# ProPrj___2025-02-25.net
KiCad netlist of a schematic drawn in EasyEDA Pro
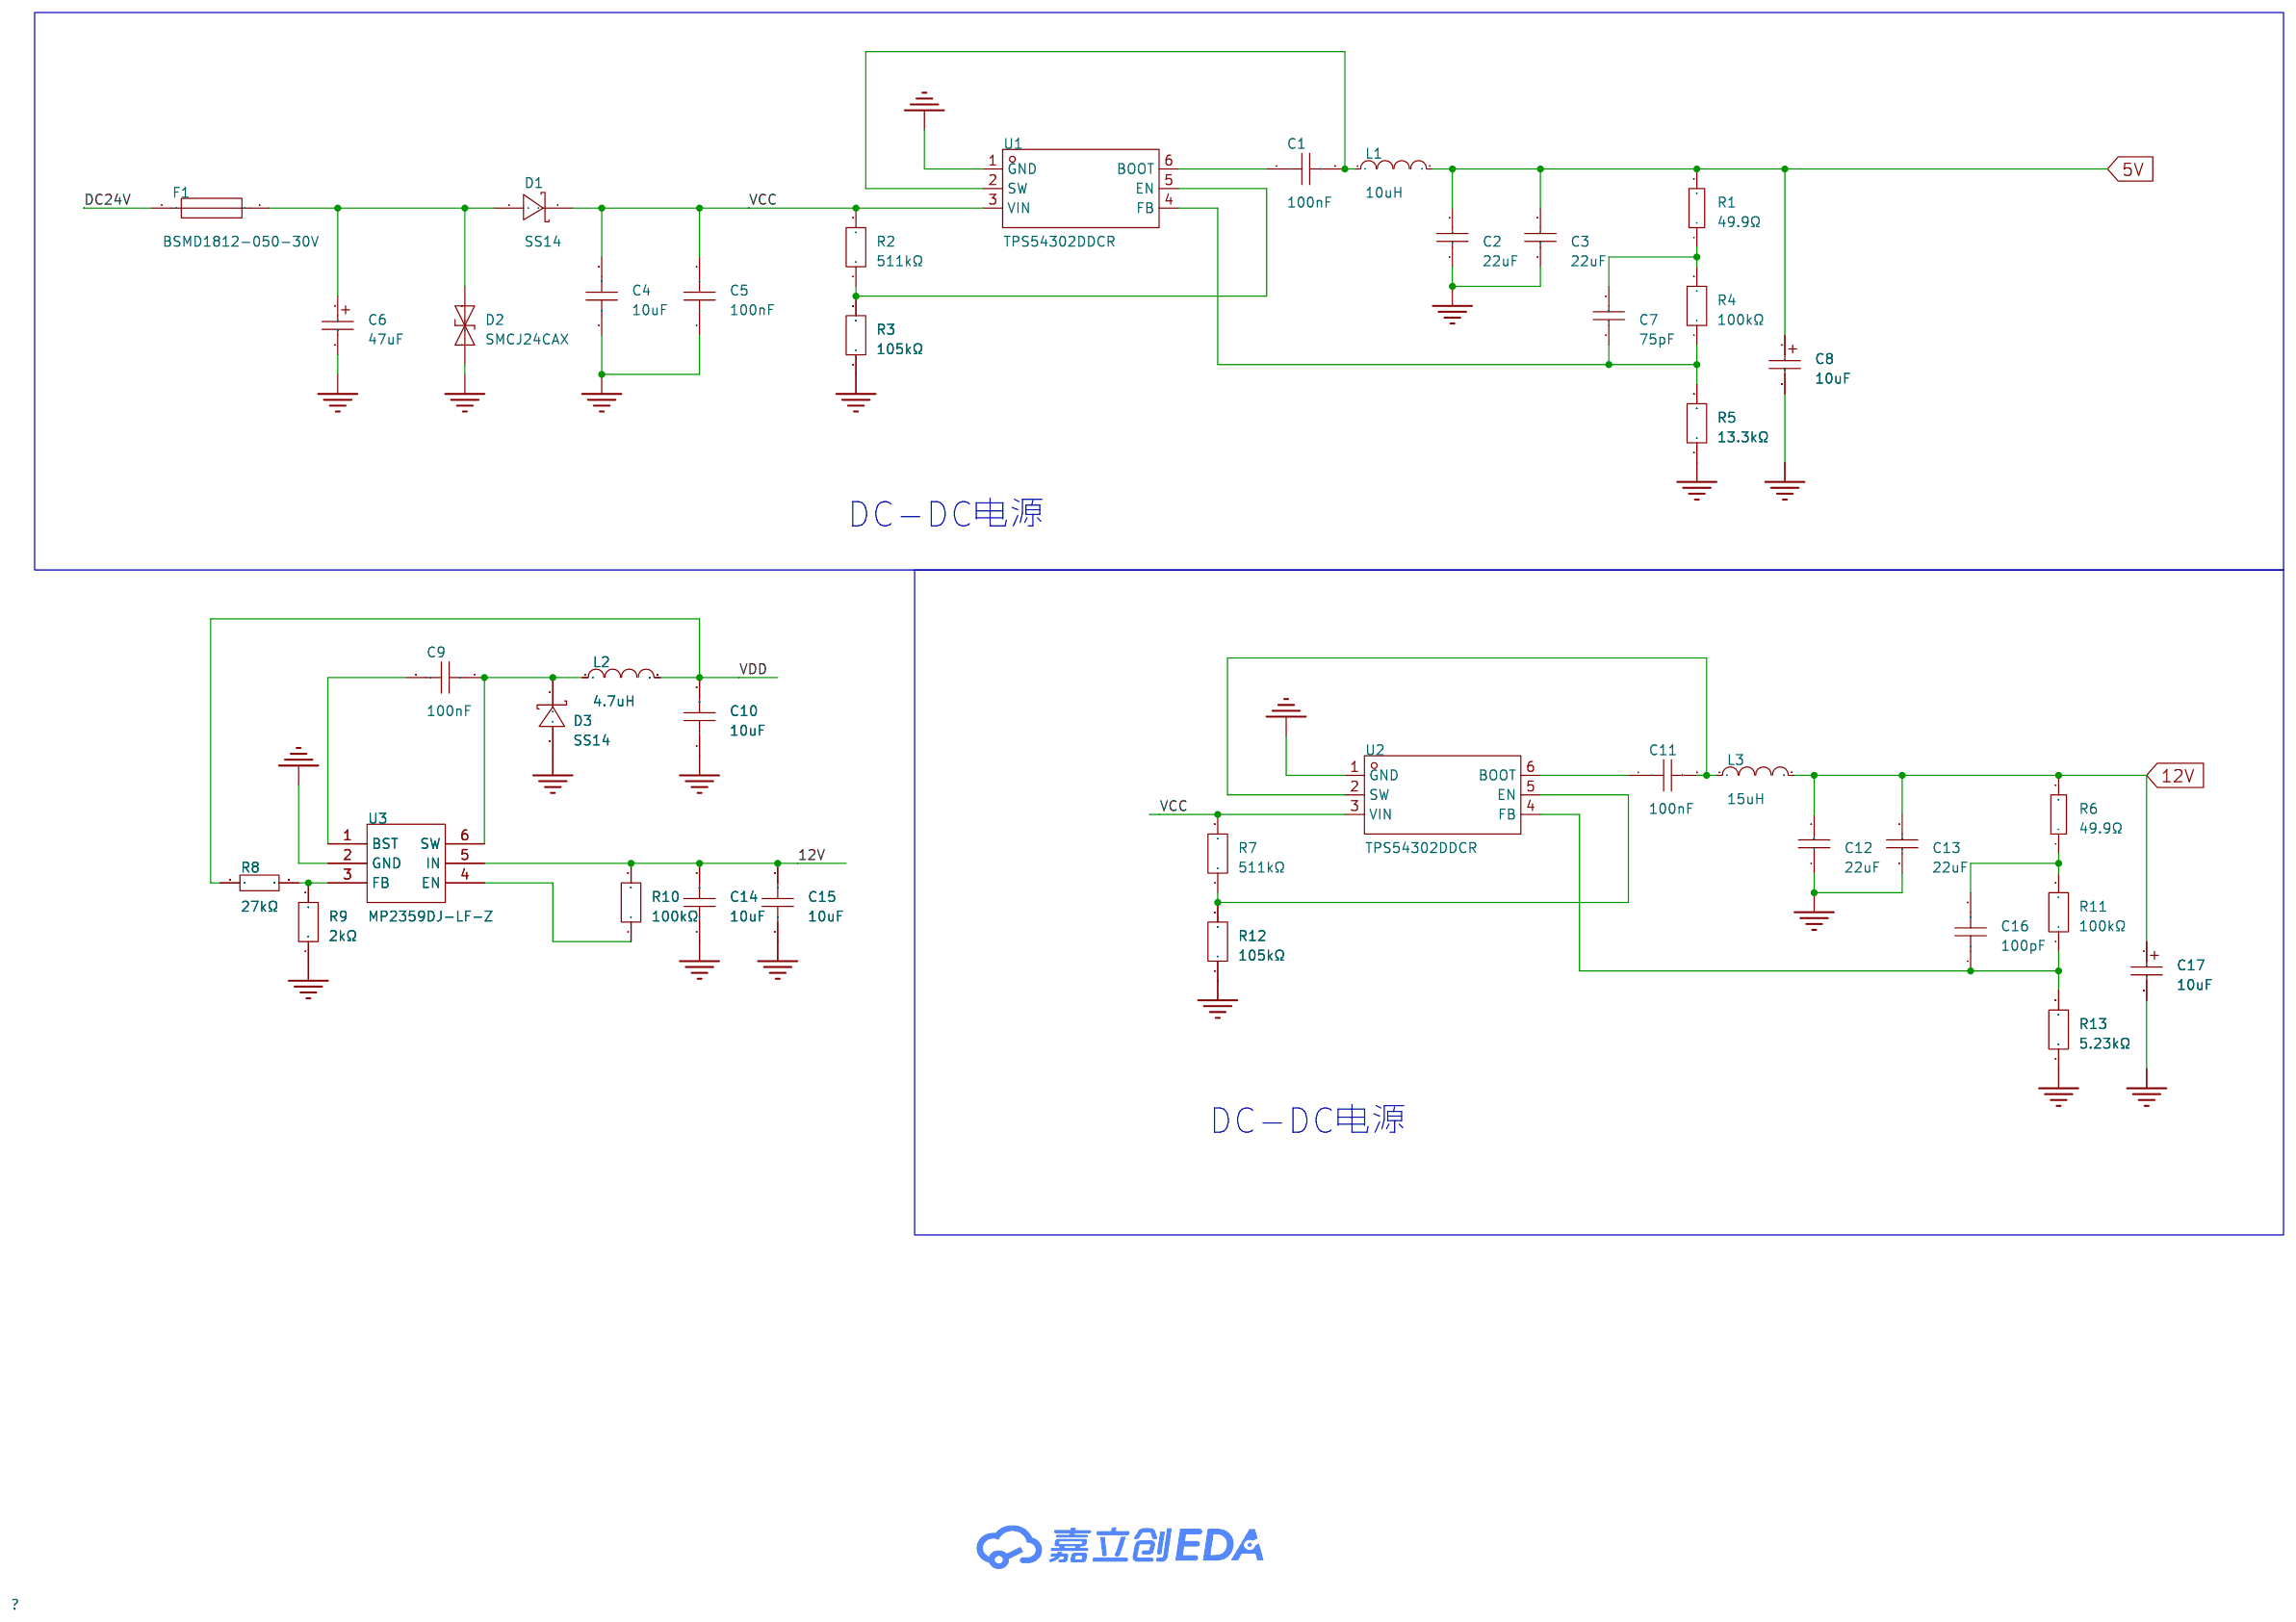
[diagram p0: P1]
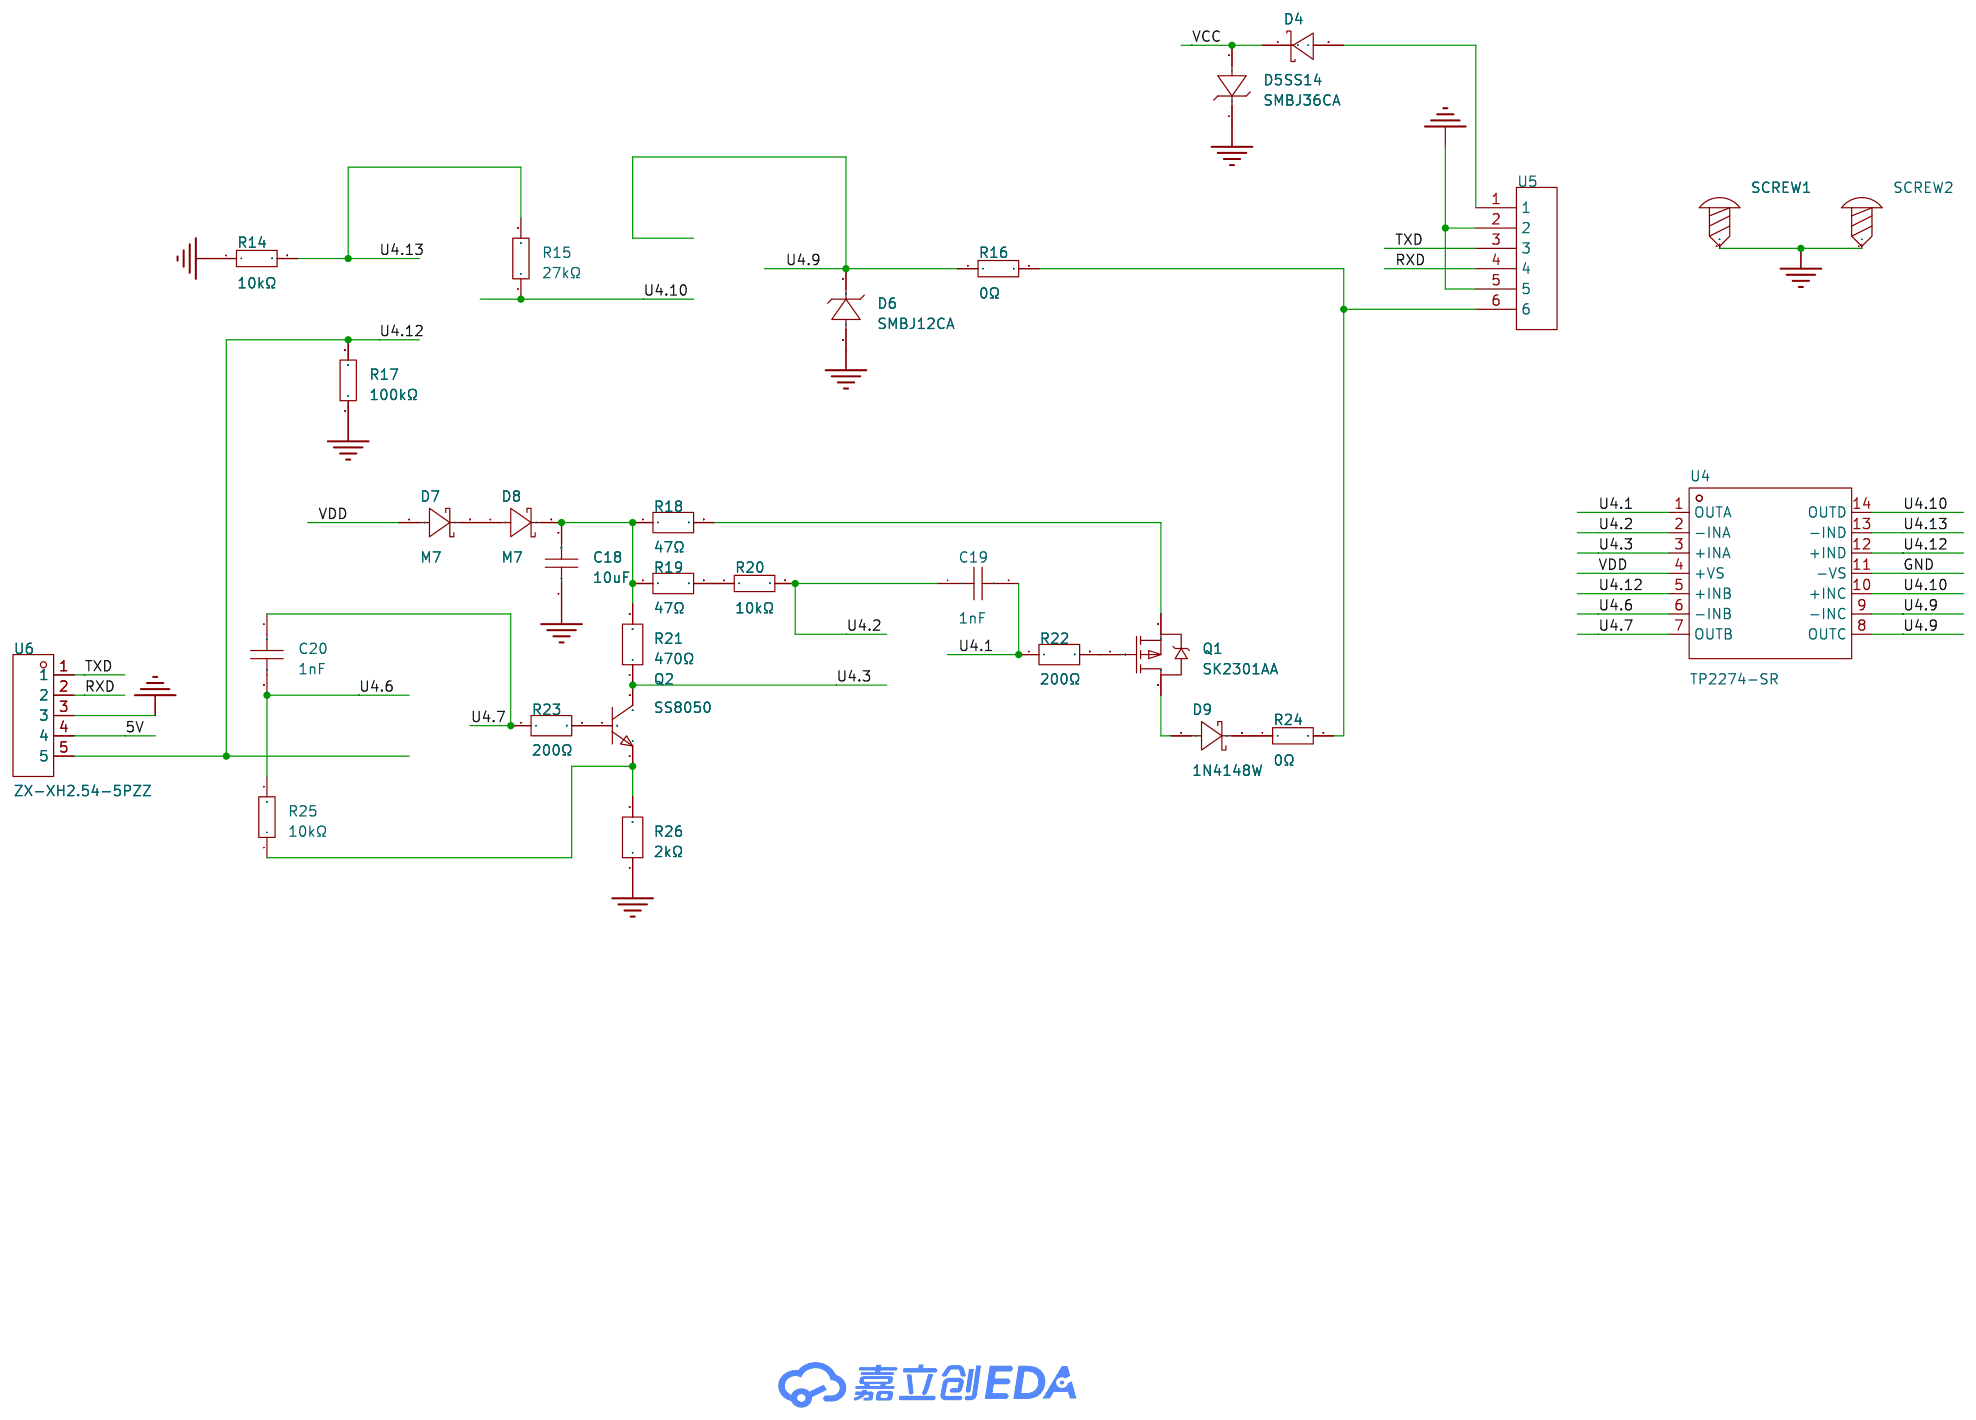
[diagram p1: P2]

(export (version "E")
  (design (tool "Eeschema 10.0.6"))
  (components
    (comp (ref "C1")
      (value "100nF")
      (footprint "easyedapro:C0402")
      (description "容值:100nF;精度:±10%;额定电压:50V;材质(温度系数):X7R;")
      (fields
        (field (name "Manufacturer Part") "GRM155R71H104KE14D")
        (field (name "Manufacturer") "muRata(村田)")
      )
      (libsource (lib "easyedapro") (part "GRM155R71H104KE14D"))
    )
    (comp (ref "C2")
      (value "22uF")
      (footprint "easyedapro:C0805")
      (description "容值:22uF;精度:±20%;额定电压:25V;材质(温度系数):X5R;")
      (fields
        (field (name "Manufacturer Part") "CC0805MKX5R8BB226")
        (field (name "Manufacturer") "YAGEO(国巨)")
      )
      (libsource (lib "easyedapro") (part "CC0805MKX5R8BB226"))
    )
    (comp (ref "C3")
      (value "22uF")
      (footprint "easyedapro:C0805")
      (description "容值:22uF;精度:±20%;额定电压:25V;材质(温度系数):X5R;")
      (fields
        (field (name "Manufacturer Part") "CC0805MKX5R8BB226")
        (field (name "Manufacturer") "YAGEO(国巨)")
      )
      (libsource (lib "easyedapro") (part "CC0805MKX5R8BB226"))
    )
    (comp (ref "C4")
      (value "10uF")
      (footprint "easyedapro:C0603")
      (description "容值:10uF;精度:±20%;额定电压:35V;材质(温度系数):X5R;")
      (fields
        (field (name "Manufacturer Part") "GRM188R6YA106MA73D")
        (field (name "Manufacturer") "muRata(村田)")
      )
      (libsource (lib "easyedapro") (part "GRM188R6YA106MA73D"))
    )
    (comp (ref "C5")
      (value "100nF")
      (footprint "easyedapro:C0402")
      (description "容值:100nF;精度:±10%;额定电压:35V;材质(温度系数):X7R;")
      (fields (field (name "Manufacturer Part") "CGA2B3X7R1V104KT0Y0F") (field (name "Manufacturer") "TDK"))
      (libsource (lib "easyedapro") (part "CGA2B3X7R1V104KT0Y0F"))
    )
    (comp (ref "C6")
      (value "47uF")
      (footprint "easyedapro:CAP-SMD_L7.3-W4.3-FD")
      (description "容值:47uF;精度:±10%;额定电压:35V;等效串联电阻:600mΩ@100kHz;")
      (fields (field (name "Manufacturer Part") "T491X476K035AT") (field (name "Manufacturer") "KEMET(基美)"))
      (libsource (lib "easyedapro") (part "T491X476K035AT"))
    )
    (comp (ref "C7")
      (value "75pF")
      (footprint "easyedapro:C0402")
      (description "容值:75pF;精度:±5%;额定电压:50V;材质(温度系数):NP0;")
      (fields
        (field (name "Manufacturer Part") "CC0402JRNPO9BN750")
        (field (name "Manufacturer") "YAGEO(国巨)")
      )
      (libsource (lib "easyedapro") (part "CC0402JRNPO9BN750"))
    )
    (comp (ref "C8")
      (value "10uF")
      (footprint "easyedapro:CASE-C_6032")
      (description "容值:10uF;精度:±10%;额定电压:35V;等效串联电阻:1.6Ω@100kHz;")
      (fields (field (name "Manufacturer Part") "TAJC106K035RNJ") (field (name "Manufacturer") "Kyocera AVX"))
      (libsource (lib "easyedapro") (part "TAJC106K035RNJ"))
    )
    (comp (ref "C9")
      (value "100nF")
      (footprint "easyedapro:C0402")
      (description "容值:100nF;精度:±10%;额定电压:35V;材质(温度系数):X7R;")
      (fields (field (name "Manufacturer Part") "CGA2B3X7R1V104KT0Y0F") (field (name "Manufacturer") "TDK"))
      (libsource (lib "easyedapro") (part "CGA2B3X7R1V104KT0Y0F"))
    )
    (comp (ref "C10")
      (value "10uF")
      (footprint "easyedapro:C0603")
      (description "容值:10uF;精度:±20%;额定电压:35V;材质(温度系数):X5R;")
      (fields
        (field (name "Manufacturer Part") "GRM188R6YA106MA73D")
        (field (name "Manufacturer") "muRata(村田)")
      )
      (libsource (lib "easyedapro") (part "GRM188R6YA106MA73D"))
    )
    (comp (ref "C11")
      (value "100nF")
      (footprint "easyedapro:C0402")
      (description "容值:100nF;精度:±10%;额定电压:50V;材质(温度系数):X7R;")
      (fields
        (field (name "Manufacturer Part") "GRM155R71H104KE14D")
        (field (name "Manufacturer") "muRata(村田)")
      )
      (libsource (lib "easyedapro") (part "GRM155R71H104KE14D"))
    )
    (comp (ref "C12")
      (value "22uF")
      (footprint "easyedapro:C0805")
      (description "容值:22uF;精度:±20%;额定电压:25V;材质(温度系数):X5R;")
      (fields
        (field (name "Manufacturer Part") "CC0805MKX5R8BB226")
        (field (name "Manufacturer") "YAGEO(国巨)")
      )
      (libsource (lib "easyedapro") (part "CC0805MKX5R8BB226"))
    )
    (comp (ref "C13")
      (value "22uF")
      (footprint "easyedapro:C0805")
      (description "容值:22uF;精度:±20%;额定电压:25V;材质(温度系数):X5R;")
      (fields
        (field (name "Manufacturer Part") "CC0805MKX5R8BB226")
        (field (name "Manufacturer") "YAGEO(国巨)")
      )
      (libsource (lib "easyedapro") (part "CC0805MKX5R8BB226"))
    )
    (comp (ref "C14")
      (value "10uF")
      (footprint "easyedapro:C0603")
      (description "容值:10uF;精度:±20%;额定电压:35V;材质(温度系数):X5R;")
      (fields
        (field (name "Manufacturer Part") "GRM188R6YA106MA73D")
        (field (name "Manufacturer") "muRata(村田)")
      )
      (libsource (lib "easyedapro") (part "GRM188R6YA106MA73D"))
    )
    (comp (ref "C15")
      (value "10uF")
      (footprint "easyedapro:C0603")
      (description "容值:10uF;精度:±20%;额定电压:35V;材质(温度系数):X5R;")
      (fields
        (field (name "Manufacturer Part") "GRM188R6YA106MA73D")
        (field (name "Manufacturer") "muRata(村田)")
      )
      (libsource (lib "easyedapro") (part "GRM188R6YA106MA73D"))
    )
    (comp (ref "C16")
      (value "100pF")
      (footprint "easyedapro:C0402")
      (description "容值:100pF;精度:±10%;额定电压:25V;材质(温度系数):X7R;")
      (fields
        (field (name "Manufacturer Part") "CC0402KRX7R8BB101")
        (field (name "Manufacturer") "YAGEO(国巨)")
      )
      (libsource (lib "easyedapro") (part "CC0402KRX7R8BB101"))
    )
    (comp (ref "C17")
      (value "10uF")
      (footprint "easyedapro:CASE-C_6032")
      (description "容值:10uF;精度:±10%;额定电压:35V;等效串联电阻:1.6Ω@100kHz;")
      (fields (field (name "Manufacturer Part") "TAJC106K035RNJ") (field (name "Manufacturer") "Kyocera AVX"))
      (libsource (lib "easyedapro") (part "TAJC106K035RNJ"))
    )
    (comp (ref "D1")
      (value "SS14")
      (footprint "easyedapro:SMA_L4.2-W2.6-LS5.3-RD")
      (description "二极管配置:独立式;正向压降(Vf):550mV@1A;直流反向耐压(Vr):40V;整流电流:1A;")
      (fields (field (name "Manufacturer") "MDD(辰达半导体)"))
      (libsource (lib "easyedapro") (part "SS14"))
    )
    (comp (ref "D2")
      (value "SMCJ24CAX")
      (footprint "easyedapro:SMC_L6.9-W5.9-LS7.9-BI")
      (description "VRWM24(V)/VBR(Min)@IT26.7(V)/VBR(Max)@IT30.7(V)/IT1(mA)/IR5(uA)/VC(Max)38.9(V)/Ipp(Max)38.6(A)")
      (fields (field (name "Manufacturer") "晶扬电子"))
      (libsource (lib "easyedapro") (part "SMCJ24CA_C3038088"))
    )
    (comp (ref "D3")
      (value "SS14")
      (footprint "easyedapro:SMA_L4.3-W2.6-LS5.2-RD")
      (description "正向压降(Vf):500mV@1A;直流反向耐压(Vr):40V;整流电流:1A;")
      (fields (field (name "Manufacturer") "onsemi(安森美)"))
      (libsource (lib "easyedapro") (part "SS14_C83852"))
    )
    (comp (ref "F1")
      (value "BSMD1812-050-30V")
      (footprint "easyedapro:F1812")
      (description "最大电压:30V;最大电流:40A;保持电流:500mA;跳闸电流:1A;")
      (fields (field (name "Manufacturer") "BHFUSE(佰宏)"))
      (libsource (lib "easyedapro") (part "BSMD1812-050-30V"))
    )
    (comp (ref "L1")
      (value "10uH")
      (footprint "easyedapro:IND-SMD_L4.4-W4.2")
      (description "电感值:10uH;精度:±20%;额定电流:1.6A;饱和电流(Isat):2.2A;类型:一体成型电感;")
      (fields (field (name "Manufacturer Part") "FXL0420-100-M") (field (name "Manufacturer") "cjiang(长江微电)"))
      (libsource (lib "easyedapro") (part "FXL0420-100-M"))
    )
    (comp (ref "L2")
      (value "4.7uH")
      (footprint "easyedapro:IND-SMD_L7.0-W6.6")
      (description "电感值:4.7uH;精度:±20%;额定电流:6A;饱和电流(Isat):9A;类型:一体成型电感;")
      (fields (field (name "Manufacturer Part") "FXL0630-4R7-M") (field (name "Manufacturer") "cjiang(长江微电)"))
      (libsource (lib "easyedapro") (part "FXL0630-4R7-M"))
    )
    (comp (ref "L3")
      (value "15uH")
      (footprint "easyedapro:IND-SMD_L4.0-W4.0")
      (description "电感值:15uH;精度:±20%;额定电流:1.2A;饱和电流(Isat):2.8A;")
      (fields
        (field (name "Manufacturer Part") "FHD4020S-150MT")
        (field (name "Manufacturer") "cjiang(长江微电)")
      )
      (libsource (lib "easyedapro") (part "FHD4020S-150MT"))
    )
    (comp (ref "R1")
      (value "49.9Ω")
      (footprint "easyedapro:R0402")
      (description "电阻类型:薄膜电阻;阻值:49.9Ω;精度:±0.1%;功率:60mW;最大工作电压:75V;温度系数:±25ppm/°C;")
      (fields (field (name "Manufacturer Part") "PTFR0402B49R9P9") (field (name "Manufacturer") "RESI(开步睿思)"))
      (libsource (lib "easyedapro") (part "PTFR0402B49R9P9"))
    )
    (comp (ref "R2")
      (value "511kΩ")
      (footprint "easyedapro:R0603")
      (description "电阻类型:薄膜电阻;阻值:511kΩ;精度:±0.1%;功率:100mW;最大工作电压:75V;温度系数:±25ppm/°C;")
      (fields (field (name "Manufacturer Part") "ARG03BTC5113") (field (name "Manufacturer") "Viking(光颉)"))
      (libsource (lib "easyedapro") (part "ARG03BTC5113"))
    )
    (comp (ref "R3")
      (value "105kΩ")
      (footprint "easyedapro:R0402")
      (description "电阻类型:薄膜电阻;阻值:105kΩ;精度:±0.1%;功率:62.5mW;温度系数:±25ppm/°C;")
      (fields (field (name "Manufacturer Part") "RT0402BRD07105KL") (field (name "Manufacturer") "YAGEO(国巨)"))
      (libsource (lib "easyedapro") (part "RT0402BRD07105KL"))
    )
    (comp (ref "R4")
      (value "100kΩ")
      (footprint "easyedapro:R0402")
      (description "电阻类型:薄膜电阻;阻值:100kΩ;精度:±0.1%;功率:62.5mW;最大工作电压:50V;温度系数:±25ppm/°C;")
      (fields (field (name "Manufacturer Part") "RT0402BRD07100KL") (field (name "Manufacturer") "YAGEO(国巨)"))
      (libsource (lib "easyedapro") (part "RT0402BRD07100KL"))
    )
    (comp (ref "R5")
      (value "13.3kΩ")
      (footprint "easyedapro:R0603")
      (description "电阻类型:薄膜电阻;阻值:13.3kΩ;精度:±0.1%;功率:100mW;最大工作电压:75V;温度系数:±25ppm/°C;")
      (fields (field (name "Manufacturer Part") "RT0603BRD0713K3L") (field (name "Manufacturer") "YAGEO(国巨)"))
      (libsource (lib "easyedapro") (part "RT0603BRD0713K3L"))
    )
    (comp (ref "R6")
      (value "49.9Ω")
      (footprint "easyedapro:R0402")
      (description "电阻类型:薄膜电阻;阻值:49.9Ω;精度:±0.1%;功率:60mW;最大工作电压:75V;温度系数:±25ppm/°C;")
      (fields (field (name "Manufacturer Part") "PTFR0402B49R9P9") (field (name "Manufacturer") "RESI(开步睿思)"))
      (libsource (lib "easyedapro") (part "PTFR0402B49R9P9"))
    )
    (comp (ref "R7")
      (value "511kΩ")
      (footprint "easyedapro:R0603")
      (description "电阻类型:薄膜电阻;阻值:511kΩ;精度:±0.1%;功率:100mW;最大工作电压:75V;温度系数:±25ppm/°C;")
      (fields (field (name "Manufacturer Part") "ARG03BTC5113") (field (name "Manufacturer") "Viking(光颉)"))
      (libsource (lib "easyedapro") (part "ARG03BTC5113"))
    )
    (comp (ref "R8")
      (value "27kΩ")
      (footprint "easyedapro:R0603")
      (description "电阻类型:薄膜电阻;阻值:27kΩ;精度:±0.1%;功率:100mW;最大工作电压:75V;温度系数:±50ppm/°C;")
      (fields (field (name "Manufacturer Part") "RT0603BRE0727KL") (field (name "Manufacturer") "YAGEO(国巨)"))
      (libsource (lib "easyedapro") (part "RT0603BRE0727KL"))
    )
    (comp (ref "R9")
      (value "2kΩ")
      (footprint "easyedapro:R0603")
      (description "电阻类型:薄膜电阻;阻值:2kΩ;精度:±0.1%;功率:100mW;温度系数:±25ppm/°C;")
      (fields (field (name "Manufacturer Part") "RT0603BRD072KL") (field (name "Manufacturer") "YAGEO(国巨)"))
      (libsource (lib "easyedapro") (part "RT0603BRD072KL"))
    )
    (comp (ref "R10")
      (value "100kΩ")
      (footprint "easyedapro:R0402")
      (description "电阻类型:薄膜电阻;阻值:100kΩ;精度:±0.1%;功率:62.5mW;最大工作电压:50V;温度系数:±25ppm/°C;")
      (fields (field (name "Manufacturer Part") "RT0402BRD07100KL") (field (name "Manufacturer") "YAGEO(国巨)"))
      (libsource (lib "easyedapro") (part "RT0402BRD07100KL"))
    )
    (comp (ref "R11")
      (value "100kΩ")
      (footprint "easyedapro:R0402")
      (description "电阻类型:薄膜电阻;阻值:100kΩ;精度:±0.1%;功率:62.5mW;最大工作电压:50V;温度系数:±25ppm/°C;")
      (fields (field (name "Manufacturer Part") "RT0402BRD07100KL") (field (name "Manufacturer") "YAGEO(国巨)"))
      (libsource (lib "easyedapro") (part "RT0402BRD07100KL"))
    )
    (comp (ref "R12")
      (value "105kΩ")
      (footprint "easyedapro:R0402")
      (description "电阻类型:薄膜电阻;阻值:105kΩ;精度:±0.1%;功率:62.5mW;温度系数:±25ppm/°C;")
      (fields (field (name "Manufacturer Part") "RT0402BRD07105KL") (field (name "Manufacturer") "YAGEO(国巨)"))
      (libsource (lib "easyedapro") (part "RT0402BRD07105KL"))
    )
    (comp (ref "R13")
      (value "5.23kΩ")
      (footprint "easyedapro:R0603")
      (description "电阻类型:薄膜电阻;阻值:5.23kΩ;精度:±0.1%;功率:100mW;温度系数:±25ppm/°C;")
      (fields (field (name "Manufacturer Part") "RT0603BRD075K23L") (field (name "Manufacturer") "YAGEO(国巨)"))
      (libsource (lib "easyedapro") (part "RT0603BRD075K23L"))
    )
    (comp (ref "U1")
      (value "TPS54302DDCR")
      (footprint "easyedapro:SOT-23-6_L2.9-W1.6-P0.95-LS2.8-BL")
      (description "功能类型:降压型;输出类型:固定;工作电压:4.5V~28V;输出电压:5V;输出电流:3A;")
      (fields (field (name "Manufacturer") "TI(德州仪器)"))
      (libsource (lib "easyedapro") (part "TPS54302DDCR_C311983"))
    )
    (comp (ref "U2")
      (value "TPS54302DDCR")
      (footprint "easyedapro:SOT-23-6_L2.9-W1.6-P0.95-LS2.8-BL")
      (description "功能类型:降压型;输出类型:固定;工作电压:4.5V~28V;输出电压:5V;输出电流:3A;")
      (fields (field (name "Manufacturer") "TI(德州仪器)"))
      (libsource (lib "easyedapro") (part "TPS54302DDCR_C311983"))
    )
    (comp (ref "U3")
      (value "MP2359DJ-LF-Z")
      (footprint "easyedapro:SOT-23-6_L2.9-W1.6-P0.95-LS2.8-BR")
      (description "功能类型:降压型;输出类型:可调;工作电压:4.5V~24V;输出电压:810mV~15V;输出电流:1.2A;")
      (fields (field (name "Manufacturer") "MPS(芯源)"))
      (libsource (lib "easyedapro") (part "MP2359DJ-LF-Z"))
    )
    (comp (ref "C18")
      (value "10uF")
      (footprint "easyedapro:C0603")
      (description "容值:10uF;精度:±20%;额定电压:35V;材质(温度系数):X5R;")
      (fields
        (field (name "Manufacturer Part") "HGC0603R5106M350NTHJ")
        (field (name "Manufacturer") "Chinocera(华瓷)")
      )
      (libsource (lib "easyedapro") (part "HGC0603R5106M350NTHJ"))
    )
    (comp (ref "C19")
      (value "1nF")
      (footprint "easyedapro:C0603")
      (description "容值:1nF;精度:±10%;额定电压:25V;材质(温度系数):X7R;")
      (fields
        (field (name "Manufacturer Part") "CC0603KRX7R8BB102")
        (field (name "Manufacturer") "YAGEO(国巨)")
      )
      (libsource (lib "easyedapro") (part "CC0603KRX7R8BB102"))
    )
    (comp (ref "C20")
      (value "1nF")
      (footprint "easyedapro:C0603")
      (description "容值:1nF;精度:±10%;额定电压:25V;材质(温度系数):X7R;")
      (fields
        (field (name "Manufacturer Part") "CC0603KRX7R8BB102")
        (field (name "Manufacturer") "YAGEO(国巨)")
      )
      (libsource (lib "easyedapro") (part "CC0603KRX7R8BB102"))
    )
    (comp (ref "D4")
      (value "SS14")
      (footprint "easyedapro:SMA_L4.3-W2.6-LS5.2-RD")
      (description "正向压降(Vf):500mV@1A;直流反向耐压(Vr):40V;整流电流:1A;")
      (fields (field (name "Manufacturer") "onsemi(安森美)"))
      (libsource (lib "easyedapro") (part "SS14_C83852"))
    )
    (comp (ref "D5")
      (value "SMBJ36CA")
      (footprint "easyedapro:SMB_L4.6-W3.6-LS5.4-RD")
      (description "极性:双向;反向截止电压(Vrwm):36V;钳位电压:58.1V;峰值脉冲电流(Ipp):10.33A;峰值脉冲功率(Ppp):600W;击穿电压:40V;")
      (fields (field (name "Manufacturer") "宏嘉诚"))
      (libsource (lib "easyedapro") (part "SMBJ36CA_C19077589"))
    )
    (comp (ref "D6")
      (value "SMBJ12CA")
      (footprint "easyedapro:SMB_L4.6-W3.6-LS5.4-RD")
      (fields (field (name "Manufacturer") "宏迦橙"))
      (libsource (lib "easyedapro") (part "SMBJ12CA_C19077566"))
    )
    (comp (ref "D7")
      (value "M7")
      (footprint "easyedapro:SMA_L4.3-W2.6-LS5.0-FD")
      (description "二极管配置:独立式;正向压降(Vf):1.1V@1A;直流反向耐压(Vr):1kV;整流电流:1A;")
      (fields (field (name "Manufacturer") "宏迦橙"))
      (libsource (lib "easyedapro") (part "M7_C7420350"))
    )
    (comp (ref "D8")
      (value "M7")
      (footprint "easyedapro:SMA_L4.3-W2.6-LS5.0-FD")
      (description "二极管配置:独立式;正向压降(Vf):1.1V@1A;直流反向耐压(Vr):1kV;整流电流:1A;")
      (fields (field (name "Manufacturer") "宏迦橙"))
      (libsource (lib "easyedapro") (part "M7_C7420350"))
    )
    (comp (ref "D9")
      (value "1N4148W")
      (footprint "easyedapro:SOD-123_L2.7-W1.6-LS3.7-FD")
      (description "二极管配置:独立式;正向压降(Vf):1.25V@150mA;直流反向耐压(Vr):100V;整流电流:150mA;反向恢复时间(trr):4ns;")
      (fields (field (name "Manufacturer") "宏迦橙"))
      (libsource (lib "easyedapro") (part "1N4148W_C7420318"))
    )
    (comp (ref "Q1")
      (value "SK2301AA")
      (footprint "easyedapro:SOT-23-3_L2.9-W1.6-P1.90-LS2.8-BR")
      (fields (field (name "Manufacturer") "SHIKUES(时科)"))
      (libsource (lib "easyedapro") (part "SK2301AA"))
    )
    (comp (ref "Q2")
      (value "SS8050")
      (footprint "easyedapro:SOT-23-3_L2.9-W1.3-P1.90-LS2.4-BR")
      (description "晶体管类型:NPN;集电极电流(Ic):1.5A;集射极击穿电压(Vceo):25V;功率(Pd):300mW;直流电流增益(hFE@Ic,Vce):120@100mA,1.0V;")
      (fields (field (name "Manufacturer") "宏迦橙"))
      (libsource (lib "easyedapro") (part "SS8050_C7420370"))
    )
    (comp (ref "R14")
      (value "10kΩ")
      (footprint "easyedapro:R0603")
      (description "电阻类型:薄膜电阻;阻值:10kΩ;精度:±0.1%;功率:100mW;最大工作电压:75V;温度系数:±25ppm/°C;")
      (fields (field (name "Manufacturer Part") "RT0603BRD0710KL") (field (name "Manufacturer") "YAGEO(国巨)"))
      (libsource (lib "easyedapro") (part "RT0603BRD0710KL"))
    )
    (comp (ref "R15")
      (value "27kΩ")
      (footprint "easyedapro:R0603")
      (description "电阻类型:薄膜电阻;阻值:27kΩ;精度:±0.1%;功率:100mW;最大工作电压:75V;温度系数:±50ppm/°C;")
      (fields (field (name "Manufacturer Part") "RT0603BRE0727KL") (field (name "Manufacturer") "YAGEO(国巨)"))
      (libsource (lib "easyedapro") (part "RT0603BRE0727KL"))
    )
    (comp (ref "R16")
      (value "0Ω")
      (footprint "easyedapro:R0603")
      (description "电阻类型:厚膜电阻;阻值:0Ω;精度:±1%;功率:100mW;最大工作电压:75V;温度系数:-;")
      (fields (field (name "Manufacturer Part") "RC0603FR-070RL") (field (name "Manufacturer") "YAGEO(国巨)"))
      (libsource (lib "easyedapro") (part "RC0603FR-070RL"))
    )
    (comp (ref "R17")
      (value "100kΩ")
      (footprint "easyedapro:R0603")
      (description "电阻类型:薄膜电阻;阻值:100kΩ;精度:±0.1%;功率:100mW;最大工作电压:75V;温度系数:±25ppm/°C;")
      (fields (field (name "Manufacturer Part") "RT0603BRD07100KL") (field (name "Manufacturer") "YAGEO(国巨)"))
      (libsource (lib "easyedapro") (part "RT0603BRD07100KL"))
    )
    (comp (ref "R18")
      (value "47Ω")
      (footprint "easyedapro:R0603")
      (description "电阻类型:薄膜电阻;阻值:47Ω;精度:±0.1%;功率:100mW;最大工作电压:75V;温度系数:±50ppm/°C;")
      (fields (field (name "Manufacturer Part") "RT0603BRE0747RL") (field (name "Manufacturer") "YAGEO(国巨)"))
      (libsource (lib "easyedapro") (part "RT0603BRE0747RL"))
    )
    (comp (ref "R19")
      (value "47Ω")
      (footprint "easyedapro:R0603")
      (description "电阻类型:薄膜电阻;阻值:47Ω;精度:±0.1%;功率:100mW;最大工作电压:75V;温度系数:±50ppm/°C;")
      (fields (field (name "Manufacturer Part") "RT0603BRE0747RL") (field (name "Manufacturer") "YAGEO(国巨)"))
      (libsource (lib "easyedapro") (part "RT0603BRE0747RL"))
    )
    (comp (ref "R20")
      (value "10kΩ")
      (footprint "easyedapro:R0603")
      (description "电阻类型:薄膜电阻;阻值:10kΩ;精度:±0.1%;功率:100mW;最大工作电压:75V;温度系数:±25ppm/°C;")
      (fields (field (name "Manufacturer Part") "RT0603BRD0710KL") (field (name "Manufacturer") "YAGEO(国巨)"))
      (libsource (lib "easyedapro") (part "RT0603BRD0710KL"))
    )
    (comp (ref "R21")
      (value "470Ω")
      (footprint "easyedapro:R0603")
      (description "电阻类型:薄膜电阻;阻值:470Ω;精度:±0.1%;功率:100mW;最大工作电压:75V;温度系数:±25ppm/°C;")
      (fields (field (name "Manufacturer Part") "RT0603BRD07470RL") (field (name "Manufacturer") "YAGEO(国巨)"))
      (libsource (lib "easyedapro") (part "RT0603BRD07470RL"))
    )
    (comp (ref "R22")
      (value "200Ω")
      (footprint "easyedapro:R0603")
      (description "电阻类型:薄膜电阻;阻值:200Ω;精度:±0.1%;功率:100mW;最大工作电压:75V;温度系数:±25ppm/°C;")
      (fields (field (name "Manufacturer Part") "RT0603BRD07200RL") (field (name "Manufacturer") "YAGEO(国巨)"))
      (libsource (lib "easyedapro") (part "RT0603BRD07200RL"))
    )
    (comp (ref "R23")
      (value "200Ω")
      (footprint "easyedapro:R0603")
      (description "电阻类型:薄膜电阻;阻值:200Ω;精度:±0.1%;功率:100mW;最大工作电压:75V;温度系数:±25ppm/°C;")
      (fields (field (name "Manufacturer Part") "RT0603BRD07200RL") (field (name "Manufacturer") "YAGEO(国巨)"))
      (libsource (lib "easyedapro") (part "RT0603BRD07200RL"))
    )
    (comp (ref "R24")
      (value "0Ω")
      (footprint "easyedapro:R0603")
      (description "电阻类型:厚膜电阻;阻值:0Ω;精度:±1%;功率:100mW;最大工作电压:75V;温度系数:-;")
      (fields (field (name "Manufacturer Part") "RC0603FR-070RL") (field (name "Manufacturer") "YAGEO(国巨)"))
      (libsource (lib "easyedapro") (part "RC0603FR-070RL"))
    )
    (comp (ref "R25")
      (value "10kΩ")
      (footprint "easyedapro:R0603")
      (description "电阻类型:薄膜电阻;阻值:10kΩ;精度:±0.1%;功率:100mW;最大工作电压:75V;温度系数:±25ppm/°C;")
      (fields (field (name "Manufacturer Part") "RT0603BRD0710KL") (field (name "Manufacturer") "YAGEO(国巨)"))
      (libsource (lib "easyedapro") (part "RT0603BRD0710KL"))
    )
    (comp (ref "R26")
      (value "2kΩ")
      (footprint "easyedapro:R0603")
      (description "电阻类型:薄膜电阻;阻值:2kΩ;精度:±0.1%;功率:100mW;温度系数:±25ppm/°C;")
      (fields (field (name "Manufacturer Part") "RT0603BRD072KL") (field (name "Manufacturer") "YAGEO(国巨)"))
      (libsource (lib "easyedapro") (part "RT0603BRD072KL"))
    )
    (comp (ref "SCREW1")
      (value "~")
      (footprint "easyedapro:M2螺丝")
      (libsource (lib "easyedapro") (part "螺丝孔"))
    )
    (comp (ref "SCREW2")
      (value "~")
      (footprint "easyedapro:M2螺丝")
      (libsource (lib "easyedapro") (part "螺丝孔"))
    )
    (comp (ref "U4")
      (value "TP2274-SR")
      (footprint "easyedapro:SOIC-14_L8.7-W3.9-P1.27-LS6.0-BL")
      (description "放大器数:四路;增益带宽积(GBP):7MHz;压摆率(SR):20V/us;")
      (fields (field (name "Manufacturer") "3PEAK"))
      (libsource (lib "easyedapro") (part "TP2274-SR"))
    )
    (comp (ref "U5")
      (value "~")
      (footprint "easyedapro:LC8+LZ8V-2.54 5PIN")
      (description "2.54节距PCB插拔连接器_P6IN_联捷")
      (libsource (lib "easyedapro") (part "LZ8V-2.54-6P"))
    )
    (comp (ref "U6")
      (value "ZX-XH2.54-5PZZ")
      (footprint "easyedapro:CONN-TH_5P-P2.50_ZX-XH2.54-5PZZ")
      (fields (field (name "Manufacturer") "Megastar(兆星)"))
      (libsource (lib "easyedapro") (part "ZX-XH2.54-5PZZ"))
    )
  )
  (nets
    (net (code "1") (name "5V") (class "Default")
      (node (ref "C2") (pin "2") (pinfunction "2_2") (pintype "input"))
      (node (ref "C3") (pin "2") (pinfunction "2_2") (pintype "input"))
      (node (ref "C8") (pin "1") (pinfunction "1_1") (pintype "input"))
      (node (ref "L1") (pin "2") (pinfunction "2_2") (pintype "unspecified"))
      (node (ref "R1") (pin "2") (pinfunction "2_2") (pintype "input"))
      (node (ref "U6") (pin "4") (pinfunction "4_4") (pintype "unspecified"))
    )
    (net (code "2") (name "12V") (class "Default")
      (node (ref "C12") (pin "2") (pinfunction "2_2") (pintype "input"))
      (node (ref "C13") (pin "2") (pinfunction "2_2") (pintype "input"))
      (node (ref "C14") (pin "2") (pinfunction "2_2") (pintype "unspecified"))
      (node (ref "C15") (pin "2") (pinfunction "2_2") (pintype "unspecified"))
      (node (ref "C17") (pin "1") (pinfunction "1_1") (pintype "input"))
      (node (ref "L3") (pin "2") (pinfunction "2_2") (pintype "unspecified"))
      (node (ref "R10") (pin "2") (pinfunction "2_2") (pintype "unspecified"))
      (node (ref "R6") (pin "2") (pinfunction "2_2") (pintype "input"))
      (node (ref "U3") (pin "5") (pinfunction "IN_5") (pintype "unspecified"))
    )
    (net (code "3") (name "DC24V") (class "Default")
      (node (ref "F1") (pin "1") (pinfunction "1_1") (pintype "unspecified"))
    )
    (net (code "4") (name "GND") (class "Default")
      (node (ref "C10") (pin "1") (pinfunction "1_1") (pintype "unspecified"))
      (node (ref "C12") (pin "1") (pinfunction "1_1") (pintype "input"))
      (node (ref "C13") (pin "1") (pinfunction "1_1") (pintype "input"))
      (node (ref "C14") (pin "1") (pinfunction "1_1") (pintype "unspecified"))
      (node (ref "C15") (pin "1") (pinfunction "1_1") (pintype "unspecified"))
      (node (ref "C17") (pin "2") (pinfunction "2_2") (pintype "input"))
      (node (ref "C18") (pin "1") (pinfunction "1_1") (pintype "unspecified"))
      (node (ref "C2") (pin "1") (pinfunction "1_1") (pintype "input"))
      (node (ref "C3") (pin "1") (pinfunction "1_1") (pintype "input"))
      (node (ref "C4") (pin "1") (pinfunction "1_1") (pintype "unspecified"))
      (node (ref "C5") (pin "1") (pinfunction "1_1") (pintype "unspecified"))
      (node (ref "C6") (pin "2") (pinfunction "2_2") (pintype "input"))
      (node (ref "C8") (pin "2") (pinfunction "2_2") (pintype "input"))
      (node (ref "D2") (pin "1") (pinfunction "K_1") (pintype "unspecified"))
      (node (ref "D3") (pin "2") (pinfunction "A_2") (pintype "unspecified"))
      (node (ref "D5") (pin "1") (pinfunction "K_1") (pintype "unspecified"))
      (node (ref "D6") (pin "2") (pinfunction "A_2") (pintype "unspecified"))
      (node (ref "R12") (pin "1") (pinfunction "1_1") (pintype "unspecified"))
      (node (ref "R13") (pin "1") (pinfunction "1_1") (pintype "unspecified"))
      (node (ref "R14") (pin "1") (pinfunction "1_1") (pintype "input"))
      (node (ref "R17") (pin "1") (pinfunction "1_1") (pintype "input"))
      (node (ref "R26") (pin "1") (pinfunction "1_1") (pintype "unspecified"))
      (node (ref "R3") (pin "1") (pinfunction "1_1") (pintype "unspecified"))
      (node (ref "R5") (pin "1") (pinfunction "1_1") (pintype "unspecified"))
      (node (ref "R9") (pin "1") (pinfunction "1_1") (pintype "unspecified"))
      (node (ref "SCREW1") (pin "1") (pinfunction "1_1") (pintype "input"))
      (node (ref "SCREW2") (pin "1") (pinfunction "1_1") (pintype "input"))
      (node (ref "U1") (pin "1") (pinfunction "GND_1") (pintype "unspecified"))
      (node (ref "U2") (pin "1") (pinfunction "GND_1") (pintype "unspecified"))
      (node (ref "U3") (pin "2") (pinfunction "GND_2") (pintype "unspecified"))
      (node (ref "U4") (pin "11") (pinfunction "-VS_11") (pintype "unspecified"))
      (node (ref "U5") (pin "2") (pinfunction "2_2") (pintype "input"))
      (node (ref "U5") (pin "5") (pinfunction "5_5") (pintype "input"))
      (node (ref "U6") (pin "3") (pinfunction "3_3") (pintype "unspecified"))
    )
    (net (code "5") (name "Net-(C7-Pad2)") (class "Default")
      (node (ref "C7") (pin "2") (pinfunction "2_2") (pintype "input"))
      (node (ref "R1") (pin "1") (pinfunction "1_1") (pintype "input"))
      (node (ref "R4") (pin "2") (pinfunction "2_2") (pintype "unspecified"))
    )
    (net (code "6") (name "Net-(C16-Pad2)") (class "Default")
      (node (ref "C16") (pin "2") (pinfunction "2_2") (pintype "unspecified"))
      (node (ref "R11") (pin "2") (pinfunction "2_2") (pintype "unspecified"))
      (node (ref "R6") (pin "1") (pinfunction "1_1") (pintype "input"))
    )
    (net (code "7") (name "Net-(D1-A)") (class "Default")
      (node (ref "C6") (pin "1") (pinfunction "1_1") (pintype "input"))
      (node (ref "D1") (pin "2") (pinfunction "A_2") (pintype "unspecified"))
      (node (ref "D2") (pin "2") (pinfunction "A_2") (pintype "unspecified"))
      (node (ref "F1") (pin "2") (pinfunction "2_2") (pintype "unspecified"))
    )
    (net (code "8") (name "Net-(D3-K)") (class "Default")
      (node (ref "C9") (pin "1") (pinfunction "1_1") (pintype "unspecified"))
      (node (ref "D3") (pin "1") (pinfunction "K_1") (pintype "unspecified"))
      (node (ref "L2") (pin "1") (pinfunction "1_1") (pintype "unspecified"))
      (node (ref "U3") (pin "6") (pinfunction "SW_6") (pintype "unspecified"))
    )
    (net (code "9") (name "Net-(D4-A)") (class "Default")
      (node (ref "D4") (pin "2") (pinfunction "A_2") (pintype "unspecified"))
      (node (ref "U5") (pin "1") (pinfunction "1_1") (pintype "input"))
    )
    (net (code "10") (name "Net-(D7-K)") (class "Default")
      (node (ref "D7") (pin "2") (pinfunction "K_2") (pintype "unspecified"))
      (node (ref "D8") (pin "1") (pinfunction "A_1") (pintype "unspecified"))
    )
    (net (code "11") (name "Net-(D8-K)") (class "Default")
      (node (ref "C18") (pin "2") (pinfunction "2_2") (pintype "unspecified"))
      (node (ref "D8") (pin "2") (pinfunction "K_2") (pintype "unspecified"))
      (node (ref "R18") (pin "1") (pinfunction "1_1") (pintype "unspecified"))
      (node (ref "R19") (pin "1") (pinfunction "1_1") (pintype "unspecified"))
      (node (ref "R21") (pin "2") (pinfunction "2_2") (pintype "unspecified"))
    )
    (net (code "12") (name "Net-(D9-A)") (class "Default")
      (node (ref "D9") (pin "1") (pinfunction "A_1") (pintype "unspecified"))
      (node (ref "Q1") (pin "3") (pinfunction "D_3") (pintype "unspecified"))
    )
    (net (code "13") (name "Net-(D9-K)") (class "Default")
      (node (ref "D9") (pin "2") (pinfunction "K_2") (pintype "unspecified"))
      (node (ref "R24") (pin "1") (pinfunction "1_1") (pintype "input"))
    )
    (net (code "14") (name "Net-(Q1-G)") (class "Default")
      (node (ref "Q1") (pin "1") (pinfunction "G_1") (pintype "unspecified"))
      (node (ref "R22") (pin "2") (pinfunction "2_2") (pintype "unspecified"))
    )
    (net (code "15") (name "Net-(Q1-S)") (class "Default")
      (node (ref "Q1") (pin "2") (pinfunction "S_2") (pintype "unspecified"))
      (node (ref "R18") (pin "2") (pinfunction "2_2") (pintype "unspecified"))
    )
    (net (code "16") (name "Net-(Q2-B)") (class "Default")
      (node (ref "Q2") (pin "1") (pinfunction "B_1") (pintype "input"))
      (node (ref "R23") (pin "2") (pinfunction "2_2") (pintype "unspecified"))
    )
    (net (code "17") (name "Net-(Q2-E)") (class "Default")
      (node (ref "Q2") (pin "2") (pinfunction "E_2") (pintype "input"))
      (node (ref "R25") (pin "1") (pinfunction "1_1") (pintype "input"))
      (node (ref "R26") (pin "2") (pinfunction "2_2") (pintype "unspecified"))
    )
    (net (code "18") (name "Net-(R16-Pad2)") (class "Default")
      (node (ref "R16") (pin "2") (pinfunction "2_2") (pintype "input"))
      (node (ref "R24") (pin "2") (pinfunction "2_2") (pintype "input"))
      (node (ref "U5") (pin "6") (pinfunction "6_6") (pintype "input"))
    )
    (net (code "19") (name "Net-(R19-Pad2)") (class "Default")
      (node (ref "R19") (pin "2") (pinfunction "2_2") (pintype "unspecified"))
      (node (ref "R20") (pin "1") (pinfunction "1_1") (pintype "input"))
    )
    (net (code "20") (name "Net-(U1-BOOT)") (class "Default")
      (node (ref "C1") (pin "1") (pinfunction "1_1") (pintype "unspecified"))
      (node (ref "U1") (pin "6") (pinfunction "BOOT_6") (pintype "unspecified"))
    )
    (net (code "21") (name "Net-(U1-EN)") (class "Default")
      (node (ref "R2") (pin "1") (pinfunction "1_1") (pintype "unspecified"))
      (node (ref "R3") (pin "2") (pinfunction "2_2") (pintype "unspecified"))
      (node (ref "U1") (pin "5") (pinfunction "EN_5") (pintype "unspecified"))
    )
    (net (code "22") (name "Net-(U1-FB)") (class "Default")
      (node (ref "C7") (pin "1") (pinfunction "1_1") (pintype "input"))
      (node (ref "R4") (pin "1") (pinfunction "1_1") (pintype "unspecified"))
      (node (ref "R5") (pin "2") (pinfunction "2_2") (pintype "unspecified"))
      (node (ref "U1") (pin "4") (pinfunction "FB_4") (pintype "unspecified"))
    )
    (net (code "23") (name "Net-(U1-SW)") (class "Default")
      (node (ref "C1") (pin "2") (pinfunction "2_2") (pintype "unspecified"))
      (node (ref "L1") (pin "1") (pinfunction "1_1") (pintype "unspecified"))
      (node (ref "U1") (pin "2") (pinfunction "SW_2") (pintype "unspecified"))
    )
    (net (code "24") (name "Net-(U2-BOOT)") (class "Default")
      (node (ref "C11") (pin "1") (pinfunction "1_1") (pintype "unspecified"))
      (node (ref "U2") (pin "6") (pinfunction "BOOT_6") (pintype "unspecified"))
    )
    (net (code "25") (name "Net-(U2-EN)") (class "Default")
      (node (ref "R12") (pin "2") (pinfunction "2_2") (pintype "unspecified"))
      (node (ref "R7") (pin "1") (pinfunction "1_1") (pintype "unspecified"))
      (node (ref "U2") (pin "5") (pinfunction "EN_5") (pintype "unspecified"))
    )
    (net (code "26") (name "Net-(U2-FB)") (class "Default")
      (node (ref "C16") (pin "1") (pinfunction "1_1") (pintype "unspecified"))
      (node (ref "R11") (pin "1") (pinfunction "1_1") (pintype "unspecified"))
      (node (ref "R13") (pin "2") (pinfunction "2_2") (pintype "unspecified"))
      (node (ref "U2") (pin "4") (pinfunction "FB_4") (pintype "unspecified"))
    )
    (net (code "27") (name "Net-(U2-SW)") (class "Default")
      (node (ref "C11") (pin "2") (pinfunction "2_2") (pintype "unspecified"))
      (node (ref "L3") (pin "1") (pinfunction "1_1") (pintype "unspecified"))
      (node (ref "U2") (pin "2") (pinfunction "SW_2") (pintype "unspecified"))
    )
    (net (code "28") (name "Net-(U3-BST)") (class "Default")
      (node (ref "C9") (pin "2") (pinfunction "2_2") (pintype "unspecified"))
      (node (ref "U3") (pin "1") (pinfunction "BST_1") (pintype "unspecified"))
    )
    (net (code "29") (name "Net-(U3-EN)") (class "Default")
      (node (ref "R10") (pin "1") (pinfunction "1_1") (pintype "unspecified"))
      (node (ref "U3") (pin "4") (pinfunction "EN_4") (pintype "unspecified"))
    )
    (net (code "30") (name "Net-(U3-FB)") (class "Default")
      (node (ref "R8") (pin "2") (pinfunction "2_2") (pintype "unspecified"))
      (node (ref "R9") (pin "2") (pinfunction "2_2") (pintype "unspecified"))
      (node (ref "U3") (pin "3") (pinfunction "FB_3") (pintype "unspecified"))
    )
    (net (code "31") (name "RXD") (class "Default")
      (node (ref "U5") (pin "4") (pinfunction "4_4") (pintype "input"))
      (node (ref "U6") (pin "2") (pinfunction "2_2") (pintype "unspecified"))
    )
    (net (code "32") (name "TXD") (class "Default")
      (node (ref "U5") (pin "3") (pinfunction "3_3") (pintype "input"))
      (node (ref "U6") (pin "1") (pinfunction "1_1") (pintype "unspecified"))
    )
    (net (code "33") (name "U4.1") (class "Default")
      (node (ref "C19") (pin "2") (pinfunction "2_2") (pintype "unspecified"))
      (node (ref "R22") (pin "1") (pinfunction "1_1") (pintype "unspecified"))
      (node (ref "U4") (pin "1") (pinfunction "OUTA_1") (pintype "unspecified"))
    )
    (net (code "34") (name "U4.2") (class "Default")
      (node (ref "C19") (pin "1") (pinfunction "1_1") (pintype "unspecified"))
      (node (ref "R20") (pin "2") (pinfunction "2_2") (pintype "input"))
      (node (ref "U4") (pin "2") (pinfunction "-INA_2") (pintype "unspecified"))
    )
    (net (code "35") (name "U4.3") (class "Default")
      (node (ref "Q2") (pin "3") (pinfunction "C_3") (pintype "input"))
      (node (ref "R21") (pin "1") (pinfunction "1_1") (pintype "unspecified"))
      (node (ref "U4") (pin "3") (pinfunction "+INA_3") (pintype "unspecified"))
    )
    (net (code "36") (name "U4.6") (class "Default")
      (node (ref "C20") (pin "2") (pinfunction "2_2") (pintype "unspecified"))
      (node (ref "R25") (pin "2") (pinfunction "2_2") (pintype "input"))
      (node (ref "U4") (pin "6") (pinfunction "-INB_6") (pintype "unspecified"))
    )
    (net (code "37") (name "U4.7") (class "Default")
      (node (ref "C20") (pin "1") (pinfunction "1_1") (pintype "unspecified"))
      (node (ref "R23") (pin "1") (pinfunction "1_1") (pintype "unspecified"))
      (node (ref "U4") (pin "7") (pinfunction "OUTB_7") (pintype "unspecified"))
    )
    (net (code "38") (name "U4.9") (class "Default")
      (node (ref "D6") (pin "1") (pinfunction "K_1") (pintype "unspecified"))
      (node (ref "R16") (pin "1") (pinfunction "1_1") (pintype "input"))
      (node (ref "U4") (pin "8") (pinfunction "OUTC_8") (pintype "unspecified"))
      (node (ref "U4") (pin "9") (pinfunction "-INC_9") (pintype "unspecified"))
    )
    (net (code "39") (name "U4.10") (class "Default")
      (node (ref "R15") (pin "1") (pinfunction "1_1") (pintype "unspecified"))
      (node (ref "U4") (pin "10") (pinfunction "+INC_10") (pintype "unspecified"))
      (node (ref "U4") (pin "14") (pinfunction "OUTD_14") (pintype "unspecified"))
    )
    (net (code "40") (name "U4.12") (class "Default")
      (node (ref "R17") (pin "2") (pinfunction "2_2") (pintype "input"))
      (node (ref "U4") (pin "12") (pinfunction "+IND_12") (pintype "unspecified"))
      (node (ref "U4") (pin "5") (pinfunction "+INB_5") (pintype "unspecified"))
      (node (ref "U6") (pin "5") (pinfunction "5_5") (pintype "unspecified"))
    )
    (net (code "41") (name "U4.13") (class "Default")
      (node (ref "R14") (pin "2") (pinfunction "2_2") (pintype "input"))
      (node (ref "R15") (pin "2") (pinfunction "2_2") (pintype "unspecified"))
      (node (ref "U4") (pin "13") (pinfunction "-IND_13") (pintype "unspecified"))
    )
    (net (code "42") (name "VCC") (class "Default")
      (node (ref "C4") (pin "2") (pinfunction "2_2") (pintype "unspecified"))
      (node (ref "C5") (pin "2") (pinfunction "2_2") (pintype "unspecified"))
      (node (ref "D1") (pin "1") (pinfunction "K_1") (pintype "unspecified"))
      (node (ref "D4") (pin "1") (pinfunction "K_1") (pintype "unspecified"))
      (node (ref "D5") (pin "2") (pinfunction "A_2") (pintype "unspecified"))
      (node (ref "R2") (pin "2") (pinfunction "2_2") (pintype "unspecified"))
      (node (ref "R7") (pin "2") (pinfunction "2_2") (pintype "unspecified"))
      (node (ref "U1") (pin "3") (pinfunction "VIN_3") (pintype "unspecified"))
      (node (ref "U2") (pin "3") (pinfunction "VIN_3") (pintype "unspecified"))
    )
    (net (code "43") (name "VDD") (class "Default")
      (node (ref "C10") (pin "2") (pinfunction "2_2") (pintype "unspecified"))
      (node (ref "D7") (pin "1") (pinfunction "A_1") (pintype "unspecified"))
      (node (ref "L2") (pin "2") (pinfunction "2_2") (pintype "unspecified"))
      (node (ref "R8") (pin "1") (pinfunction "1_1") (pintype "unspecified"))
      (node (ref "U4") (pin "4") (pinfunction "+VS_4") (pintype "unspecified"))
    )
  )
)
